# Master.net
KiCad netlist of a schematic drawn in Altium Designer
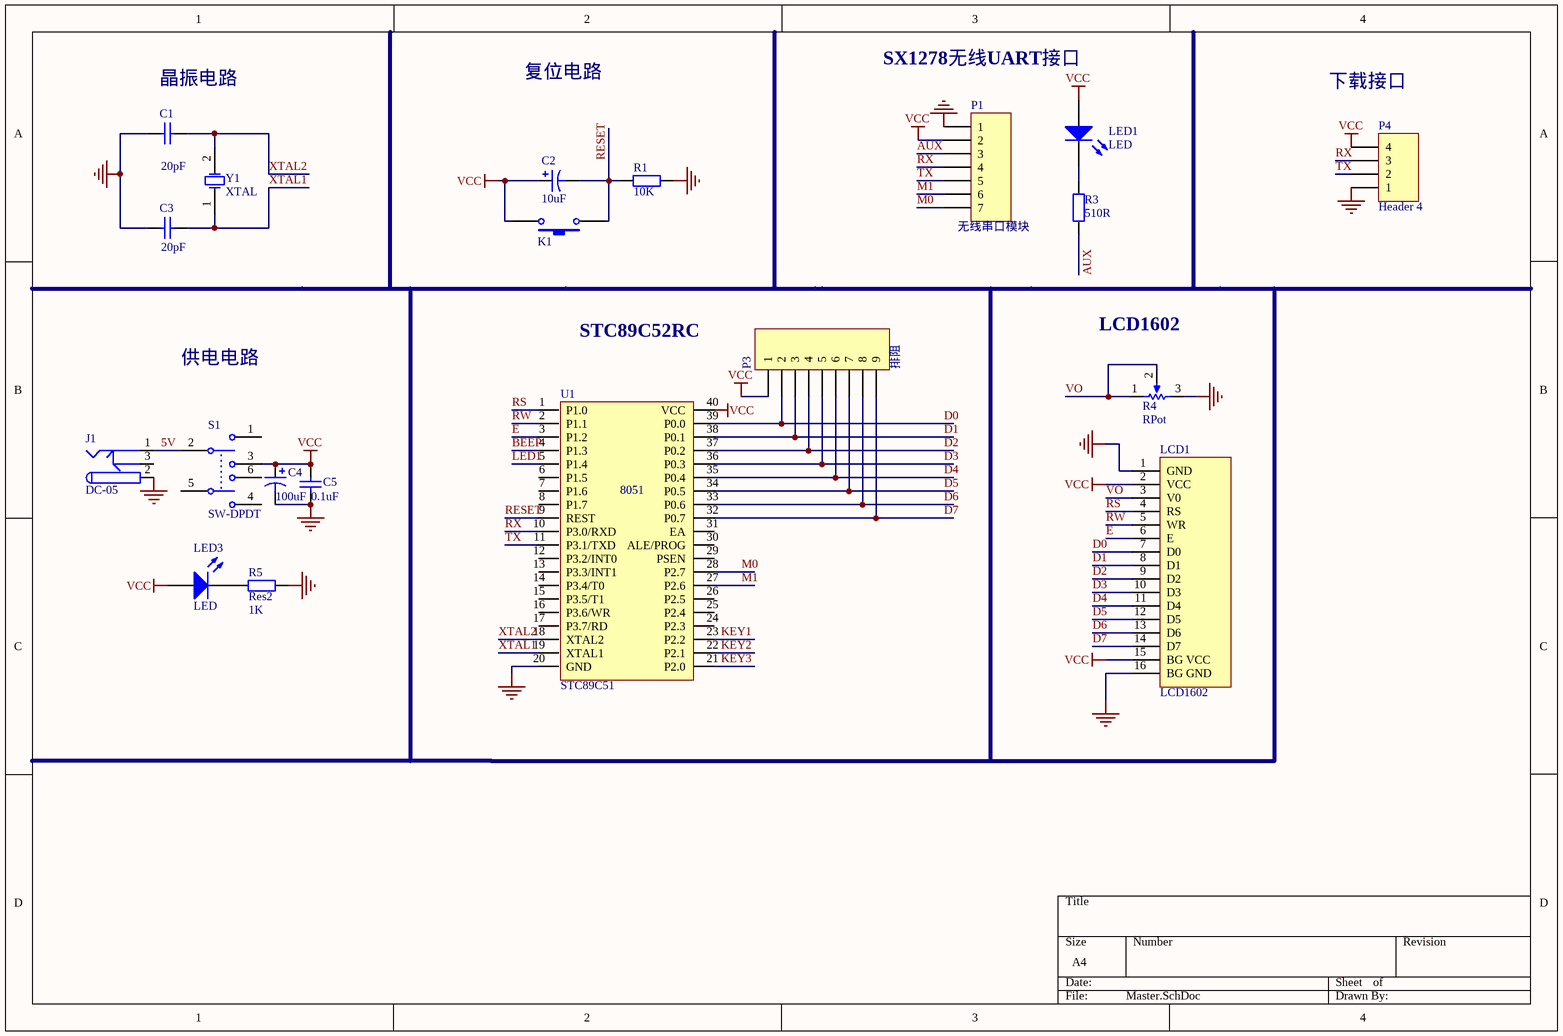
[diagram p0: Master.SchDoc]

(export (version "E")
  (design (tool "Eeschema 10.0.6"))
  (components
    (comp (ref "C1")
      (value "20pF")
      (footprint "RAD-0.1")
      (description "Capacitor")
      (fields (field (name "Comment") "Cap") (field (name "PUBLISHER") "Altium Limited"))
      (libsource (lib "Miscellaneous Devices") (part "Cap"))
    )
    (comp (ref "C2")
      (value "10uF")
      (footprint "RB.1/.2")
      (description "Polarized Capacitor (Radial)")
      (fields (field (name "Comment") "Cap Pol1") (field (name "PUBLISHER") "Altium Limited"))
      (libsource (lib "Miscellaneous Devices") (part "Cap Pol1"))
    )
    (comp (ref "C3")
      (value "20pF")
      (footprint "RAD-0.1")
      (description "Capacitor")
      (fields (field (name "Comment") "Cap") (field (name "PUBLISHER") "Altium Limited"))
      (libsource (lib "Miscellaneous Devices") (part "Cap"))
    )
    (comp (ref "C4")
      (value "100uF")
      (footprint "RB.1/.2")
      (description "Polarized Capacitor (Radial)")
      (fields (field (name "Comment") "Cap Pol1") (field (name "PUBLISHER") "Altium Limited"))
      (libsource (lib "Miscellaneous Devices") (part "Cap Pol1"))
    )
    (comp (ref "C5")
      (value "0.1uF")
      (footprint "RAD-0.1")
      (description "Capacitor")
      (fields (field (name "Comment") "Cap") (field (name "PUBLISHER") "Altium Limited"))
      (libsource (lib "Miscellaneous Devices") (part "Cap"))
    )
    (comp (ref "J1") (value "DC-05") (footprint "DC-05") (libsource (lib "My library") (part "DC-05")))
    (comp (ref "K1") (value "四脚按键") (footprint "四脚按键") (libsource (lib "My library") (part "四脚按键")))
    (comp (ref "LCD1")
      (value "LCD1602")
      (footprint "LCD1602")
      (libsource (lib "My library") (part "LCD1602"))
    )
    (comp (ref "LED1") (value "LED") (footprint "LED") (libsource (lib "My library") (part "LED")))
    (comp (ref "LED3") (value "LED") (footprint "LED") (libsource (lib "My library") (part "LED")))
    (comp (ref "P1")
      (value "无线串口模块")
      (footprint "AS32-TTL-100")
      (description "Header, 7-Pin")
      (fields (field (name "PUBLISHER") "Altium Limited"))
      (libsource (lib "Miscellaneous Connectors") (part "Header 7"))
    )
    (comp (ref "P3")
      (value "排阻")
      (footprint "HDR1X9")
      (description "Header, 9-Pin")
      (fields (field (name "PUBLISHER") "Altium Limited"))
      (libsource (lib "Miscellaneous Connectors") (part "Header 9"))
    )
    (comp (ref "P4")
      (value "Header 4")
      (footprint "HDR1X4")
      (description "Header, 4-Pin")
      (fields (field (name "PUBLISHER") "Altium Limited"))
      (libsource (lib "Miscellaneous Connectors") (part "Header 4"))
    )
    (comp (ref "R1")
      (value "10K")
      (footprint "AXIAL-0.4")
      (description "Resistor")
      (fields (field (name "Comment") "Res2") (field (name "PUBLISHER") "Altium Limited"))
      (libsource (lib "") (part "Res2_1"))
    )
    (comp (ref "R3")
      (value "510R")
      (footprint "AXIAL-0.4")
      (description "Resistor")
      (fields (field (name "Comment") "Res2") (field (name "PUBLISHER") "Altium Limited"))
      (libsource (lib "") (part "Res2_2"))
    )
    (comp (ref "R4") (value "RPot") (footprint "RPot") (libsource (lib "My library") (part "RPOT")))
    (comp (ref "R5")
      (value "Res2")
      (footprint "AXIAL-0.4")
      (description "Resistor")
      (fields (field (name "ALTIUM_VALUE") "1K") (field (name "PUBLISHER") "Altium Limited"))
      (libsource (lib "Miscellaneous Devices") (part "Res2"))
    )
    (comp (ref "S1")
      (value "SW-DPDT")
      (footprint "SWITCH_B1")
      (description "单刀双掷开关")
      (fields (field (name "PUBLISHER") "Altium Limited"))
      (libsource (lib "Fszhang") (part "SW-DPDT"))
    )
    (comp (ref "U1") (value "STC89C51") (footprint "DIP-40") (libsource (lib "My library") (part "STC89C51")))
    (comp (ref "Y1")
      (value "XTAL")
      (footprint "XTAL_US")
      (description "Crystal Oscillator")
      (fields (field (name "PUBLISHER") "Altium Limited"))
      (libsource (lib "Miscellaneous Devices") (part "XTAL"))
    )
  )
  (nets
    (net (code "1") (name "/5V") (class "Default")
      (node (ref "J1") (pin "1") (pinfunction "1_1") (pintype "passive"))
      (node (ref "S1") (pin "2") (pinfunction "2_2") (pintype "passive"))
    )
    (net (code "2") (name "/AUX") (class "Default")
      (node (ref "P1") (pin "3") (pinfunction "3_3") (pintype "passive"))
      (node (ref "R3") (pin "1") (pinfunction "1_1") (pintype "passive"))
    )
    (net (code "3") (name "/BEEP") (class "Default")
      (node (ref "U1") (pin "4") (pinfunction "P1.3_4") (pintype "passive"))
    )
    (net (code "4") (name "/D0") (class "Default")
      (node (ref "LCD1") (pin "7") (pinfunction "D0_7") (pintype "power_in"))
      (node (ref "P3") (pin "2") (pinfunction "2_2") (pintype "passive"))
      (node (ref "U1") (pin "39") (pinfunction "P0.0_39") (pintype "passive"))
    )
    (net (code "5") (name "/D1") (class "Default")
      (node (ref "LCD1") (pin "8") (pinfunction "D1_8") (pintype "power_in"))
      (node (ref "P3") (pin "3") (pinfunction "3_3") (pintype "passive"))
      (node (ref "U1") (pin "38") (pinfunction "P0.1_38") (pintype "passive"))
    )
    (net (code "6") (name "/D2") (class "Default")
      (node (ref "LCD1") (pin "9") (pinfunction "D2_9") (pintype "power_in"))
      (node (ref "P3") (pin "4") (pinfunction "4_4") (pintype "passive"))
      (node (ref "U1") (pin "37") (pinfunction "P0.2_37") (pintype "passive"))
    )
    (net (code "7") (name "/D3") (class "Default")
      (node (ref "LCD1") (pin "10") (pinfunction "D3_10") (pintype "power_in"))
      (node (ref "P3") (pin "5") (pinfunction "5_5") (pintype "passive"))
      (node (ref "U1") (pin "36") (pinfunction "P0.3_36") (pintype "passive"))
    )
    (net (code "8") (name "/D4") (class "Default")
      (node (ref "LCD1") (pin "11") (pinfunction "D4_11") (pintype "power_in"))
      (node (ref "P3") (pin "6") (pinfunction "6_6") (pintype "passive"))
      (node (ref "U1") (pin "35") (pinfunction "P0.4_35") (pintype "passive"))
    )
    (net (code "9") (name "/D5") (class "Default")
      (node (ref "LCD1") (pin "12") (pinfunction "D5_12") (pintype "power_in"))
      (node (ref "P3") (pin "7") (pinfunction "7_7") (pintype "passive"))
      (node (ref "U1") (pin "34") (pinfunction "P0.5_34") (pintype "passive"))
    )
    (net (code "10") (name "/D6") (class "Default")
      (node (ref "LCD1") (pin "13") (pinfunction "D6_13") (pintype "power_in"))
      (node (ref "P3") (pin "8") (pinfunction "8_8") (pintype "passive"))
      (node (ref "U1") (pin "33") (pinfunction "P0.6_33") (pintype "passive"))
    )
    (net (code "11") (name "/D7") (class "Default")
      (node (ref "LCD1") (pin "14") (pinfunction "D7_14") (pintype "power_in"))
      (node (ref "P3") (pin "9") (pinfunction "9_9") (pintype "passive"))
      (node (ref "U1") (pin "32") (pinfunction "P0.7_32") (pintype "passive"))
    )
    (net (code "12") (name "/E") (class "Default")
      (node (ref "LCD1") (pin "6") (pinfunction "E_6") (pintype "power_in"))
      (node (ref "U1") (pin "3") (pinfunction "P1.2_3") (pintype "passive"))
    )
    (net (code "13") (name "/KEY1") (class "Default")
      (node (ref "U1") (pin "23") (pinfunction "P2.2_23") (pintype "passive"))
    )
    (net (code "14") (name "/KEY2") (class "Default")
      (node (ref "U1") (pin "22") (pinfunction "P2.1_22") (pintype "passive"))
    )
    (net (code "15") (name "/KEY3") (class "Default")
      (node (ref "U1") (pin "21") (pinfunction "P2.0_21") (pintype "passive"))
    )
    (net (code "16") (name "/LED1") (class "Default")
      (node (ref "U1") (pin "5") (pinfunction "P1.4_5") (pintype "passive"))
    )
    (net (code "17") (name "/M0") (class "Default")
      (node (ref "P1") (pin "7") (pinfunction "7_7") (pintype "passive"))
      (node (ref "U1") (pin "28") (pinfunction "P2.7_28") (pintype "passive"))
    )
    (net (code "18") (name "/M1") (class "Default")
      (node (ref "P1") (pin "6") (pinfunction "6_6") (pintype "passive"))
      (node (ref "U1") (pin "27") (pinfunction "P2.6_27") (pintype "passive"))
    )
    (net (code "19") (name "/RESET") (class "Default")
      (node (ref "C2") (pin "2") (pinfunction "2_2") (pintype "passive"))
      (node (ref "K1") (pin "2") (pinfunction "2_2") (pintype "passive"))
      (node (ref "R1") (pin "2") (pinfunction "2_2") (pintype "passive"))
      (node (ref "U1") (pin "9") (pinfunction "REST_9") (pintype "passive"))
    )
    (net (code "20") (name "/RS") (class "Default")
      (node (ref "LCD1") (pin "4") (pinfunction "RS_4") (pintype "power_in"))
      (node (ref "U1") (pin "1") (pinfunction "P1.0_1") (pintype "passive"))
    )
    (net (code "21") (name "/RW") (class "Default")
      (node (ref "LCD1") (pin "5") (pinfunction "WR_5") (pintype "power_in"))
      (node (ref "U1") (pin "2") (pinfunction "P1.1_2") (pintype "passive"))
    )
    (net (code "22") (name "/RX") (class "Default")
      (node (ref "P1") (pin "4") (pinfunction "4_4") (pintype "passive"))
      (node (ref "P4") (pin "3") (pinfunction "3_3") (pintype "passive"))
      (node (ref "U1") (pin "10") (pinfunction "P3.0/RXD_10") (pintype "passive"))
    )
    (net (code "23") (name "/TX") (class "Default")
      (node (ref "P1") (pin "5") (pinfunction "5_5") (pintype "passive"))
      (node (ref "P4") (pin "2") (pinfunction "2_2") (pintype "passive"))
      (node (ref "U1") (pin "11") (pinfunction "P3.1/TXD_11") (pintype "passive"))
    )
    (net (code "24") (name "/VO") (class "Default")
      (node (ref "LCD1") (pin "3") (pinfunction "V0_3") (pintype "power_in"))
      (node (ref "R4") (pin "1") (pinfunction "1_1") (pintype "passive"))
      (node (ref "R4") (pin "2") (pinfunction "2_2") (pintype "passive"))
    )
    (net (code "25") (name "/XTAL1") (class "Default")
      (node (ref "C3") (pin "1") (pinfunction "1_1") (pintype "passive"))
      (node (ref "U1") (pin "19") (pinfunction "XTAL1_19") (pintype "passive"))
      (node (ref "Y1") (pin "1") (pinfunction "OSC1_1") (pintype "passive"))
    )
    (net (code "26") (name "/XTAL2") (class "Default")
      (node (ref "C1") (pin "1") (pinfunction "1_1") (pintype "passive"))
      (node (ref "U1") (pin "18") (pinfunction "XTAL2_18") (pintype "passive"))
      (node (ref "Y1") (pin "2") (pinfunction "OSC2_2") (pintype "passive"))
    )
    (net (code "27") (name "GND") (class "Default")
      (node (ref "C1") (pin "2") (pinfunction "2_2") (pintype "passive"))
      (node (ref "C3") (pin "2") (pinfunction "2_2") (pintype "passive"))
      (node (ref "C4") (pin "2") (pinfunction "2_2") (pintype "passive"))
      (node (ref "C5") (pin "1") (pinfunction "1_1") (pintype "passive"))
      (node (ref "J1") (pin "2") (pinfunction "2_2") (pintype "passive"))
      (node (ref "LCD1") (pin "1") (pinfunction "GND_1") (pintype "power_in"))
      (node (ref "LCD1") (pin "16") (pinfunction "BG_GND_16") (pintype "power_in"))
      (node (ref "P1") (pin "1") (pinfunction "1_1") (pintype "passive"))
      (node (ref "P4") (pin "1") (pinfunction "1_1") (pintype "passive"))
      (node (ref "R1") (pin "1") (pinfunction "1_1") (pintype "passive"))
      (node (ref "R4") (pin "3") (pinfunction "3_3") (pintype "passive"))
      (node (ref "R5") (pin "2") (pinfunction "2_2") (pintype "passive"))
      (node (ref "U1") (pin "20") (pinfunction "GND_20") (pintype "passive"))
    )
    (net (code "28") (name "Net-(LED1-Pad2)") (class "Default")
      (node (ref "LED1") (pin "2") (pinfunction "2_2") (pintype "passive"))
      (node (ref "R3") (pin "2") (pinfunction "2_2") (pintype "passive"))
    )
    (net (code "29") (name "Net-(LED3-Pad2)") (class "Default")
      (node (ref "LED3") (pin "2") (pinfunction "2_2") (pintype "passive"))
      (node (ref "R5") (pin "1") (pinfunction "1_1") (pintype "passive"))
    )
    (net (code "30") (name "VCC") (class "Default")
      (node (ref "C2") (pin "1") (pinfunction "1_1") (pintype "passive"))
      (node (ref "C4") (pin "1") (pinfunction "1_1") (pintype "passive"))
      (node (ref "C5") (pin "2") (pinfunction "2_2") (pintype "passive"))
      (node (ref "K1") (pin "1") (pinfunction "1_1") (pintype "passive"))
      (node (ref "LCD1") (pin "15") (pinfunction "BG_VCC_15") (pintype "power_in"))
      (node (ref "LCD1") (pin "2") (pinfunction "VCC_2") (pintype "power_in"))
      (node (ref "LED1") (pin "1") (pinfunction "1_1") (pintype "passive"))
      (node (ref "LED3") (pin "1") (pinfunction "1_1") (pintype "passive"))
      (node (ref "P1") (pin "2") (pinfunction "2_2") (pintype "passive"))
      (node (ref "P3") (pin "1") (pinfunction "1_1") (pintype "passive"))
      (node (ref "P4") (pin "4") (pinfunction "4_4") (pintype "passive"))
      (node (ref "S1") (pin "3") (pinfunction "3_3") (pintype "passive"))
      (node (ref "U1") (pin "40") (pinfunction "VCC_40") (pintype "passive"))
    )
    (net (code "31") (name "unconnected-(J1-Pad3)") (class "Default")
      (node (ref "J1") (pin "3") (pinfunction "3_3") (pintype "passive"))
    )
    (net (code "32") (name "unconnected-(S1-Pad1)") (class "Default")
      (node (ref "S1") (pin "1") (pinfunction "1_1") (pintype "passive"))
    )
    (net (code "33") (name "unconnected-(S1-Pad4)") (class "Default")
      (node (ref "S1") (pin "4") (pinfunction "4_4") (pintype "passive"))
    )
    (net (code "34") (name "unconnected-(S1-Pad5)") (class "Default")
      (node (ref "S1") (pin "5") (pinfunction "5_5") (pintype "passive"))
    )
    (net (code "35") (name "unconnected-(S1-Pad6)") (class "Default")
      (node (ref "S1") (pin "6") (pinfunction "6_6") (pintype "passive"))
    )
    (net (code "36") (name "unconnected-(U1-ALE{slash}PROG-Pad30)") (class "Default")
      (node (ref "U1") (pin "30") (pinfunction "ALE/PROG_30") (pintype "passive"))
    )
    (net (code "37") (name "unconnected-(U1-EA-Pad31)") (class "Default")
      (node (ref "U1") (pin "31") (pinfunction "EA_31") (pintype "passive"))
    )
    (net (code "38") (name "unconnected-(U1-P1.5-Pad6)") (class "Default")
      (node (ref "U1") (pin "6") (pinfunction "P1.5_6") (pintype "passive"))
    )
    (net (code "39") (name "unconnected-(U1-P1.6-Pad7)") (class "Default")
      (node (ref "U1") (pin "7") (pinfunction "P1.6_7") (pintype "passive"))
    )
    (net (code "40") (name "unconnected-(U1-P1.7-Pad8)") (class "Default")
      (node (ref "U1") (pin "8") (pinfunction "P1.7_8") (pintype "passive"))
    )
    (net (code "41") (name "unconnected-(U1-P2.3-Pad24)") (class "Default")
      (node (ref "U1") (pin "24") (pinfunction "P2.3_24") (pintype "passive"))
    )
    (net (code "42") (name "unconnected-(U1-P2.4-Pad25)") (class "Default")
      (node (ref "U1") (pin "25") (pinfunction "P2.4_25") (pintype "passive"))
    )
    (net (code "43") (name "unconnected-(U1-P2.5-Pad26)") (class "Default")
      (node (ref "U1") (pin "26") (pinfunction "P2.5_26") (pintype "passive"))
    )
    (net (code "44") (name "unconnected-(U1-P3.2{slash}INT0-Pad12)") (class "Default")
      (node (ref "U1") (pin "12") (pinfunction "P3.2/INT0_12") (pintype "passive"))
    )
    (net (code "45") (name "unconnected-(U1-P3.3{slash}INT1-Pad13)") (class "Default")
      (node (ref "U1") (pin "13") (pinfunction "P3.3/INT1_13") (pintype "passive"))
    )
    (net (code "46") (name "unconnected-(U1-P3.4{slash}T0-Pad14)") (class "Default")
      (node (ref "U1") (pin "14") (pinfunction "P3.4/T0_14") (pintype "passive"))
    )
    (net (code "47") (name "unconnected-(U1-P3.5{slash}T1-Pad15)") (class "Default")
      (node (ref "U1") (pin "15") (pinfunction "P3.5/T1_15") (pintype "passive"))
    )
    (net (code "48") (name "unconnected-(U1-P3.6{slash}WR-Pad16)") (class "Default")
      (node (ref "U1") (pin "16") (pinfunction "P3.6/WR_16") (pintype "passive"))
    )
    (net (code "49") (name "unconnected-(U1-P3.7{slash}RD-Pad17)") (class "Default")
      (node (ref "U1") (pin "17") (pinfunction "P3.7/RD_17") (pintype "passive"))
    )
    (net (code "50") (name "unconnected-(U1-PSEN-Pad29)") (class "Default")
      (node (ref "U1") (pin "29") (pinfunction "PSEN_29") (pintype "passive"))
    )
  )
)
